# simple-door-controller-12v-rly-v1.net
KiCad netlist of a schematic drawn in EAGLE
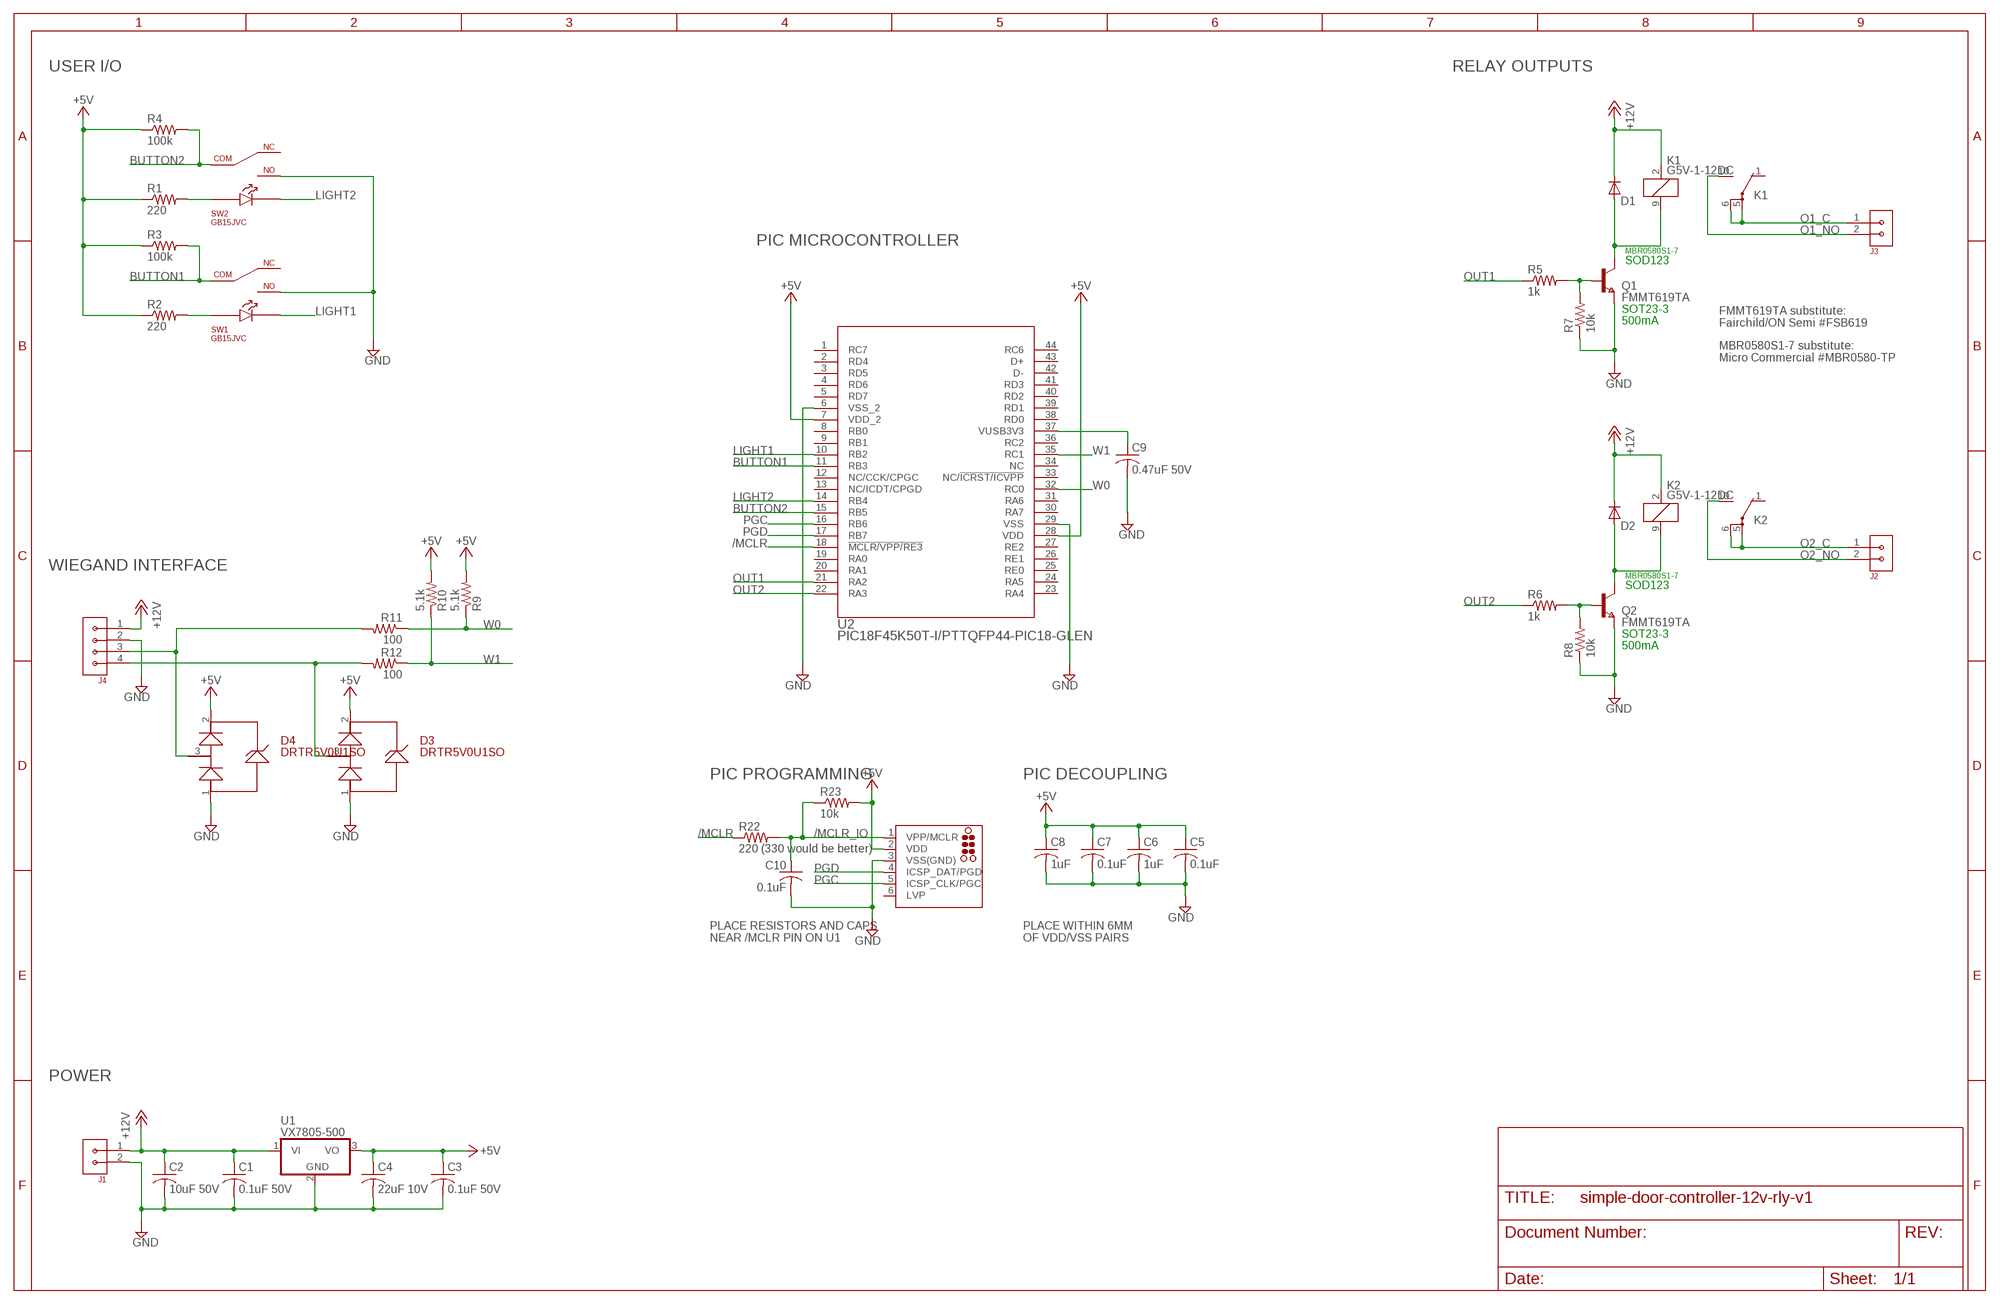
[diagram p0: schematic, sheet 1]

(export (version "E")
  (design (tool "Eeschema 10.0.6"))
  (components
    (comp (ref "C1")
      (value "0.1uF 50V")
      (footprint "eagle-import:C1206K")
      (fields (field (name "MFR") "KEMET") (field (name "MFR_PART_NO") "C1206S104M5RACTU"))
      (libsource (lib "eagle-import") (part "C-USC1206K"))
    )
    (comp (ref "C2")
      (value "10uF 50V")
      (footprint "eagle-import:C1210K")
      (fields (field (name "MFR") "KEMET") (field (name "MFR_PART_NO") "C1210C106K5RACTU"))
      (libsource (lib "eagle-import") (part "C-USC1210K"))
    )
    (comp (ref "C3")
      (value "0.1uF 50V")
      (footprint "eagle-import:C1206K")
      (fields (field (name "MFR") "KEMET") (field (name "MFR_PART_NO") "C1206S104M5RACTU"))
      (libsource (lib "eagle-import") (part "C-USC1206K"))
    )
    (comp (ref "C4")
      (value "22uF 10V")
      (footprint "eagle-import:C1206K")
      (fields (field (name "MFR") "KEMET") (field (name "MFR_PART_NO") "C1206C226K8RAC7800"))
      (libsource (lib "eagle-import") (part "C-USC1206K"))
    )
    (comp (ref "C5")
      (value "0.1uF")
      (footprint "eagle-import:C0603K")
      (libsource (lib "eagle-import") (part "C-USC0603K"))
    )
    (comp (ref "C6")
      (value "1uF")
      (footprint "eagle-import:C0603K")
      (libsource (lib "eagle-import") (part "C-USC0603K"))
    )
    (comp (ref "C7")
      (value "0.1uF")
      (footprint "eagle-import:C0603K")
      (libsource (lib "eagle-import") (part "C-USC0603K"))
    )
    (comp (ref "C8")
      (value "1uF")
      (footprint "eagle-import:C0603K")
      (libsource (lib "eagle-import") (part "C-USC0603K"))
    )
    (comp (ref "C9")
      (value "0.47uF 50V")
      (footprint "eagle-import:C1206K")
      (fields (field (name "MFR") "KEMET") (field (name "MFR_PART_NO") "C1206C474K5RACTU"))
      (libsource (lib "eagle-import") (part "C-USC1206K"))
    )
    (comp (ref "C10")
      (value "0.1uF")
      (footprint "eagle-import:C0603K")
      (libsource (lib "eagle-import") (part "C-USC0603K"))
    )
    (comp (ref "D1")
      (value "1N4148W-TP")
      (footprint "eagle-import:SOD123")
      (fields (field (name "MFR") "DIODES INC") (field (name "MFR_PART_NO") "MBR0580S1-7"))
      (libsource (lib "eagle-import") (part "DIODE-SOD123"))
    )
    (comp (ref "D2")
      (value "1N4148W-TP")
      (footprint "eagle-import:SOD123")
      (fields (field (name "MFR") "DIODES INC") (field (name "MFR_PART_NO") "MBR0580S1-7"))
      (libsource (lib "eagle-import") (part "DIODE-SOD123"))
    )
    (comp (ref "D3")
      (value "DRTR5V0U1SO")
      (footprint "eagle-import:SOT23-3")
      (libsource (lib "eagle-import") (part "DRTR5V0U1SO"))
    )
    (comp (ref "D4")
      (value "DRTR5V0U1SO")
      (footprint "eagle-import:SOT23-3")
      (libsource (lib "eagle-import") (part "DRTR5V0U1SO"))
    )
    (comp (ref "DEBUG")
      (value "TC2030-MCP-NL")
      (footprint "eagle-import:TC2030-MCP-NL")
      (libsource (lib "eagle-import") (part "TC2030-MCP-NL"))
    )
    (comp (ref "J1")
      (value "CON-3.81MM-1X2-PHOENIX")
      (footprint "eagle-import:CON-PHOENIX-3.81-1X2-RA")
      (libsource (lib "eagle-import") (part "CON-3.81MM-1X2-PHOENIX"))
    )
    (comp (ref "J2")
      (value "CON-3.81MM-1X2-PHOENIX")
      (footprint "eagle-import:CON-PHOENIX-3.81-1X2-RA")
      (libsource (lib "eagle-import") (part "CON-3.81MM-1X2-PHOENIX"))
    )
    (comp (ref "J3")
      (value "CON-3.81MM-1X2-PHOENIX")
      (footprint "eagle-import:CON-PHOENIX-3.81-1X2-RA")
      (libsource (lib "eagle-import") (part "CON-3.81MM-1X2-PHOENIX"))
    )
    (comp (ref "J4")
      (value "CON-3.81MM-1X4-PHOENIX-1803293")
      (footprint "eagle-import:CON-PHOENIX-1803293-3.81-1X4")
      (libsource (lib "eagle-import") (part "CON-3.81MM-1X4-PHOENIX-1803293"))
    )
    (comp (ref "K1")
      (value "G5V-1-12DC")
      (footprint "eagle-import:G5V1")
      (fields
        (field (name "MPN") "G5V-1-DC24")
        (field (name "MFR") "OMRON")
        (field (name "MFR_PART_NO") "G5V-1-DC5")
      )
      (libsource (lib "eagle-import") (part "G5V1"))
    )
    (comp (ref "K2")
      (value "G5V-1-12DC")
      (footprint "eagle-import:G5V1")
      (fields
        (field (name "MPN") "G5V-1-DC24")
        (field (name "MFR") "OMRON")
        (field (name "MFR_PART_NO") "G5V-1-DC5")
      )
      (libsource (lib "eagle-import") (part "G5V1"))
    )
    (comp (ref "Q1")
      (value "FMMT619TA")
      (footprint "eagle-import:SOT-23")
      (fields (field (name "MPN") "DSS20201L-7") (field (name "MFR") "DIODES INC"))
      (libsource (lib "eagle-import") (part "NPNSOT23"))
    )
    (comp (ref "Q2")
      (value "FMMT619TA")
      (footprint "eagle-import:SOT-23")
      (fields (field (name "MPN") "DSS20201L-7") (field (name "MFR") "DIODES INC"))
      (libsource (lib "eagle-import") (part "NPNSOT23"))
    )
    (comp (ref "R1")
      (value "220")
      (footprint "eagle-import:R0603")
      (libsource (lib "eagle-import") (part "R-US_R0603"))
    )
    (comp (ref "R2")
      (value "220")
      (footprint "eagle-import:R0603")
      (libsource (lib "eagle-import") (part "R-US_R0603"))
    )
    (comp (ref "R3")
      (value "100k")
      (footprint "eagle-import:R0603")
      (libsource (lib "eagle-import") (part "R-US_R0603"))
    )
    (comp (ref "R4")
      (value "100k")
      (footprint "eagle-import:R0603")
      (libsource (lib "eagle-import") (part "R-US_R0603"))
    )
    (comp (ref "R5")
      (value "1k")
      (footprint "eagle-import:R0603")
      (fields (field (name "MFR") "BOURNS") (field (name "MFR_PART_NO") "CR1206-JW-102ELF"))
      (libsource (lib "eagle-import") (part "R-US_R0603"))
    )
    (comp (ref "R6")
      (value "1k")
      (footprint "eagle-import:R0603")
      (fields (field (name "MFR") "BOURNS") (field (name "MFR_PART_NO") "CR1206-JW-102ELF"))
      (libsource (lib "eagle-import") (part "R-US_R0603"))
    )
    (comp (ref "R7")
      (value "10k")
      (footprint "eagle-import:R0603")
      (fields (field (name "MFR") "BOURNS") (field (name "MFR_PART_NO") "CR1206-JW-102ELF"))
      (libsource (lib "eagle-import") (part "R-US_R0603"))
    )
    (comp (ref "R8")
      (value "10k")
      (footprint "eagle-import:R0603")
      (fields (field (name "MFR") "BOURNS") (field (name "MFR_PART_NO") "CR1206-JW-102ELF"))
      (libsource (lib "eagle-import") (part "R-US_R0603"))
    )
    (comp (ref "R9")
      (value "5.1k")
      (footprint "eagle-import:R0603")
      (fields (field (name "MFR") "BOURNS") (field (name "MFR_PART_NO") "CR1206-JW-102ELF"))
      (libsource (lib "eagle-import") (part "R-US_R0603"))
    )
    (comp (ref "R10")
      (value "5.1k")
      (footprint "eagle-import:R0603")
      (fields (field (name "MFR") "BOURNS") (field (name "MFR_PART_NO") "CR1206-JW-102ELF"))
      (libsource (lib "eagle-import") (part "R-US_R0603"))
    )
    (comp (ref "R11")
      (value "100")
      (footprint "eagle-import:R0603")
      (fields (field (name "MFR") "BOURNS") (field (name "MFR_PART_NO") "CR1206-JW-102ELF"))
      (libsource (lib "eagle-import") (part "R-US_R0603"))
    )
    (comp (ref "R12")
      (value "100")
      (footprint "eagle-import:R0603")
      (fields (field (name "MFR") "BOURNS") (field (name "MFR_PART_NO") "CR1206-JW-102ELF"))
      (libsource (lib "eagle-import") (part "R-US_R0603"))
    )
    (comp (ref "R22")
      (value "220 (330 would be better)")
      (footprint "eagle-import:R0603")
      (libsource (lib "eagle-import") (part "R-US_R0603"))
    )
    (comp (ref "R23")
      (value "10k")
      (footprint "eagle-import:R0603")
      (libsource (lib "eagle-import") (part "R-US_R0603"))
    )
    (comp (ref "SW1")
      (value "GB15JVC")
      (footprint "eagle-import:GB15JHC")
      (libsource (lib "eagle-import") (part "GB15JHC"))
    )
    (comp (ref "SW2")
      (value "GB15JVC")
      (footprint "eagle-import:GB15JHC")
      (libsource (lib "eagle-import") (part "GB15JHC"))
    )
    (comp (ref "U1")
      (value "VX7805-500")
      (footprint "eagle-import:CUI-78XX-500")
      (libsource (lib "eagle-import") (part "CUI-V7803-500"))
    )
    (comp (ref "U2")
      (value "PIC18F45K50T-I/PTTQFP44-PIC18-GLEN")
      (footprint "eagle-import:TQFP44-PIC18-GLEN")
      (libsource (lib "eagle-import") (part "PIC18F45K50T-I/PTTQFP44-PIC18-GLEN"))
    )
  )
  (nets
    (net (code "1") (name "+5V") (class "Default")
      (node (ref "C3") (pin "1") (pinfunction "1_1") (pintype "passive"))
      (node (ref "C4") (pin "1") (pinfunction "1_1") (pintype "passive"))
      (node (ref "C5") (pin "1") (pinfunction "1_1") (pintype "passive"))
      (node (ref "C6") (pin "1") (pinfunction "1_1") (pintype "passive"))
      (node (ref "C7") (pin "1") (pinfunction "1_1") (pintype "passive"))
      (node (ref "C8") (pin "1") (pinfunction "1_1") (pintype "passive"))
      (node (ref "D3") (pin "2") (pinfunction "2_2") (pintype "bidirectional"))
      (node (ref "D4") (pin "2") (pinfunction "2_2") (pintype "bidirectional"))
      (node (ref "DEBUG") (pin "2") (pinfunction "VDD_2") (pintype "power_in"))
      (node (ref "R1") (pin "1") (pinfunction "1_1") (pintype "passive"))
      (node (ref "R10") (pin "2") (pinfunction "2_2") (pintype "passive"))
      (node (ref "R2") (pin "1") (pinfunction "1_1") (pintype "passive"))
      (node (ref "R23") (pin "2") (pinfunction "2_2") (pintype "passive"))
      (node (ref "R3") (pin "1") (pinfunction "1_1") (pintype "passive"))
      (node (ref "R4") (pin "1") (pinfunction "1_1") (pintype "passive"))
      (node (ref "R9") (pin "2") (pinfunction "2_2") (pintype "passive"))
      (node (ref "U1") (pin "3") (pinfunction "VO_3") (pintype "passive"))
      (node (ref "U2") (pin "28") (pinfunction "VDD_28") (pintype "power_in"))
      (node (ref "U2") (pin "7") (pinfunction "VDD_2_7") (pintype "power_in"))
    )
    (net (code "2") (name "+12V") (class "Default")
      (node (ref "C1") (pin "1") (pinfunction "1_1") (pintype "passive"))
      (node (ref "C2") (pin "1") (pinfunction "1_1") (pintype "passive"))
      (node (ref "D1") (pin "C") (pinfunction "C_C") (pintype "passive"))
      (node (ref "D2") (pin "C") (pinfunction "C_C") (pintype "passive"))
      (node (ref "J1") (pin "1") (pinfunction "1_1") (pintype "bidirectional"))
      (node (ref "J4") (pin "1") (pinfunction "1_1") (pintype "bidirectional"))
      (node (ref "K1") (pin "2") (pinfunction "1_2") (pintype "passive"))
      (node (ref "K2") (pin "2") (pinfunction "1_2") (pintype "passive"))
      (node (ref "U1") (pin "1") (pinfunction "VI_1") (pintype "input"))
    )
    (net (code "3") (name "/BUTTON1") (class "Default")
      (node (ref "R3") (pin "2") (pinfunction "2_2") (pintype "passive"))
      (node (ref "SW1") (pin "5") (pinfunction "5_5") (pintype "bidirectional"))
      (node (ref "U2") (pin "11") (pinfunction "RB3_11") (pintype "bidirectional"))
    )
    (net (code "4") (name "/BUTTON2") (class "Default")
      (node (ref "R4") (pin "2") (pinfunction "2_2") (pintype "passive"))
      (node (ref "SW2") (pin "5") (pinfunction "5_5") (pintype "bidirectional"))
      (node (ref "U2") (pin "15") (pinfunction "RB5_15") (pintype "bidirectional"))
    )
    (net (code "5") (name "/LIGHT1") (class "Default")
      (node (ref "SW1") (pin "3") (pinfunction "3_3") (pintype "bidirectional"))
      (node (ref "U2") (pin "10") (pinfunction "RB2_10") (pintype "bidirectional"))
    )
    (net (code "6") (name "/LIGHT2") (class "Default")
      (node (ref "SW2") (pin "3") (pinfunction "3_3") (pintype "bidirectional"))
      (node (ref "U2") (pin "14") (pinfunction "RB4_14") (pintype "bidirectional"))
    )
    (net (code "7") (name "/O1_C") (class "Default")
      (node (ref "J3") (pin "1") (pinfunction "1_1") (pintype "bidirectional"))
      (node (ref "K1") (pin "5") (pinfunction "P_5") (pintype "passive"))
      (node (ref "K1") (pin "6") (pinfunction "P_6") (pintype "passive"))
    )
    (net (code "8") (name "/O1_NO") (class "Default")
      (node (ref "J3") (pin "2") (pinfunction "2_2") (pintype "bidirectional"))
      (node (ref "K1") (pin "10") (pinfunction "S_10") (pintype "passive"))
    )
    (net (code "9") (name "/O2_C") (class "Default")
      (node (ref "J2") (pin "1") (pinfunction "1_1") (pintype "bidirectional"))
      (node (ref "K2") (pin "5") (pinfunction "P_5") (pintype "passive"))
      (node (ref "K2") (pin "6") (pinfunction "P_6") (pintype "passive"))
    )
    (net (code "10") (name "/O2_NO") (class "Default")
      (node (ref "J2") (pin "2") (pinfunction "2_2") (pintype "bidirectional"))
      (node (ref "K2") (pin "10") (pinfunction "S_10") (pintype "passive"))
    )
    (net (code "11") (name "/OUT1") (class "Default")
      (node (ref "R5") (pin "1") (pinfunction "1_1") (pintype "passive"))
      (node (ref "U2") (pin "21") (pinfunction "RA2_21") (pintype "bidirectional"))
    )
    (net (code "12") (name "/OUT2") (class "Default")
      (node (ref "R6") (pin "1") (pinfunction "1_1") (pintype "passive"))
      (node (ref "U2") (pin "22") (pinfunction "RA3_22") (pintype "bidirectional"))
    )
    (net (code "13") (name "/PGC") (class "Default")
      (node (ref "DEBUG") (pin "5") (pinfunction "ICSP_CLK/PGC_5") (pintype "output"))
      (node (ref "U2") (pin "16") (pinfunction "RB6_16") (pintype "bidirectional"))
    )
    (net (code "14") (name "/PGD") (class "Default")
      (node (ref "DEBUG") (pin "4") (pinfunction "ICSP_DAT/PGD_4") (pintype "bidirectional"))
      (node (ref "U2") (pin "17") (pinfunction "RB7_17") (pintype "bidirectional"))
    )
    (net (code "15") (name "/W0") (class "Default")
      (node (ref "R11") (pin "1") (pinfunction "1_1") (pintype "passive"))
      (node (ref "R9") (pin "1") (pinfunction "1_1") (pintype "passive"))
      (node (ref "U2") (pin "32") (pinfunction "RC0_32") (pintype "bidirectional"))
    )
    (net (code "16") (name "/W1") (class "Default")
      (node (ref "R10") (pin "1") (pinfunction "1_1") (pintype "passive"))
      (node (ref "R12") (pin "1") (pinfunction "1_1") (pintype "passive"))
      (node (ref "U2") (pin "35") (pinfunction "RC1_35") (pintype "bidirectional"))
    )
    (net (code "17") (name "/{slash}MCLR") (class "Default")
      (node (ref "R22") (pin "1") (pinfunction "1_1") (pintype "passive"))
      (node (ref "U2") (pin "18") (pinfunction "~{MCLR/VPP/RE3}_18") (pintype "bidirectional"))
    )
    (net (code "18") (name "/{slash}MCLR_IO") (class "Default")
      (node (ref "C10") (pin "1") (pinfunction "1_1") (pintype "passive"))
      (node (ref "DEBUG") (pin "1") (pinfunction "VPP/MCLR_1") (pintype "passive"))
      (node (ref "R22") (pin "2") (pinfunction "2_2") (pintype "passive"))
      (node (ref "R23") (pin "1") (pinfunction "1_1") (pintype "passive"))
    )
    (net (code "19") (name "GND") (class "Default")
      (node (ref "C1") (pin "2") (pinfunction "2_2") (pintype "passive"))
      (node (ref "C10") (pin "2") (pinfunction "2_2") (pintype "passive"))
      (node (ref "C2") (pin "2") (pinfunction "2_2") (pintype "passive"))
      (node (ref "C3") (pin "2") (pinfunction "2_2") (pintype "passive"))
      (node (ref "C4") (pin "2") (pinfunction "2_2") (pintype "passive"))
      (node (ref "C5") (pin "2") (pinfunction "2_2") (pintype "passive"))
      (node (ref "C6") (pin "2") (pinfunction "2_2") (pintype "passive"))
      (node (ref "C7") (pin "2") (pinfunction "2_2") (pintype "passive"))
      (node (ref "C8") (pin "2") (pinfunction "2_2") (pintype "passive"))
      (node (ref "C9") (pin "2") (pinfunction "2_2") (pintype "passive"))
      (node (ref "D3") (pin "1") (pinfunction "3_1") (pintype "bidirectional"))
      (node (ref "D4") (pin "1") (pinfunction "3_1") (pintype "bidirectional"))
      (node (ref "DEBUG") (pin "3") (pinfunction "VSS(GND)_3") (pintype "power_in"))
      (node (ref "J1") (pin "2") (pinfunction "2_2") (pintype "bidirectional"))
      (node (ref "J4") (pin "2") (pinfunction "2_2") (pintype "bidirectional"))
      (node (ref "Q1") (pin "2") (pinfunction "E_2") (pintype "passive"))
      (node (ref "Q2") (pin "2") (pinfunction "E_2") (pintype "passive"))
      (node (ref "R7") (pin "1") (pinfunction "1_1") (pintype "passive"))
      (node (ref "R8") (pin "1") (pinfunction "1_1") (pintype "passive"))
      (node (ref "SW1") (pin "4") (pinfunction "4_4") (pintype "bidirectional"))
      (node (ref "SW2") (pin "4") (pinfunction "4_4") (pintype "bidirectional"))
      (node (ref "U1") (pin "2") (pinfunction "GND_2") (pintype "passive"))
      (node (ref "U2") (pin "29") (pinfunction "VSS_29") (pintype "power_in"))
      (node (ref "U2") (pin "6") (pinfunction "VSS_2_6") (pintype "power_in"))
    )
    (net (code "20") (name "Net-(D3-1)") (class "Default")
      (node (ref "D3") (pin "3") (pinfunction "1_3") (pintype "bidirectional"))
      (node (ref "J4") (pin "4") (pinfunction "4_4") (pintype "bidirectional"))
      (node (ref "R12") (pin "2") (pinfunction "2_2") (pintype "passive"))
    )
    (net (code "21") (name "Net-(D4-1)") (class "Default")
      (node (ref "D4") (pin "3") (pinfunction "1_3") (pintype "bidirectional"))
      (node (ref "J4") (pin "3") (pinfunction "3_3") (pintype "bidirectional"))
      (node (ref "R11") (pin "2") (pinfunction "2_2") (pintype "passive"))
    )
    (net (code "22") (name "Net-(K1A-2)") (class "Default")
      (node (ref "D1") (pin "A") (pinfunction "A_A") (pintype "passive"))
      (node (ref "K1") (pin "9") (pinfunction "2_9") (pintype "passive"))
      (node (ref "Q1") (pin "1") (pinfunction "C_1") (pintype "passive"))
    )
    (net (code "23") (name "Net-(K2A-2)") (class "Default")
      (node (ref "D2") (pin "A") (pinfunction "A_A") (pintype "passive"))
      (node (ref "K2") (pin "9") (pinfunction "2_9") (pintype "passive"))
      (node (ref "Q2") (pin "1") (pinfunction "C_1") (pintype "passive"))
    )
    (net (code "24") (name "Net-(Q1-B)") (class "Default")
      (node (ref "Q1") (pin "3") (pinfunction "B_3") (pintype "passive"))
      (node (ref "R5") (pin "2") (pinfunction "2_2") (pintype "passive"))
      (node (ref "R7") (pin "2") (pinfunction "2_2") (pintype "passive"))
    )
    (net (code "25") (name "Net-(Q2-B)") (class "Default")
      (node (ref "Q2") (pin "3") (pinfunction "B_3") (pintype "passive"))
      (node (ref "R6") (pin "2") (pinfunction "2_2") (pintype "passive"))
      (node (ref "R8") (pin "2") (pinfunction "2_2") (pintype "passive"))
    )
    (net (code "26") (name "Net-(R1-Pad2)") (class "Default")
      (node (ref "R1") (pin "2") (pinfunction "2_2") (pintype "passive"))
      (node (ref "SW2") (pin "1") (pinfunction "1_1") (pintype "bidirectional"))
    )
    (net (code "27") (name "Net-(R2-Pad2)") (class "Default")
      (node (ref "R2") (pin "2") (pinfunction "2_2") (pintype "passive"))
      (node (ref "SW1") (pin "1") (pinfunction "1_1") (pintype "bidirectional"))
    )
    (net (code "28") (name "Net-(U2-VUSB3V3)") (class "Default")
      (node (ref "C9") (pin "1") (pinfunction "1_1") (pintype "passive"))
      (node (ref "U2") (pin "37") (pinfunction "VUSB3V3_37") (pintype "power_in"))
    )
    (net (code "29") (name "unconnected-(DEBUG-LVP-Pad6)") (class "Default")
      (node (ref "DEBUG") (pin "6") (pinfunction "LVP_6") (pintype "bidirectional"))
    )
    (net (code "30") (name "unconnected-(K1B-O-Pad1)") (class "Default")
      (node (ref "K1") (pin "1") (pinfunction "O_1") (pintype "passive"))
    )
    (net (code "31") (name "unconnected-(K2B-O-Pad1)") (class "Default")
      (node (ref "K2") (pin "1") (pinfunction "O_1") (pintype "passive"))
    )
    (net (code "32") (name "unconnected-(SW1-Pad6)") (class "Default")
      (node (ref "SW1") (pin "6") (pinfunction "6_6") (pintype "bidirectional"))
    )
    (net (code "33") (name "unconnected-(SW2-Pad6)") (class "Default")
      (node (ref "SW2") (pin "6") (pinfunction "6_6") (pintype "bidirectional"))
    )
    (net (code "34") (name "unconnected-(U2-D+-Pad43)") (class "Default")
      (node (ref "U2") (pin "43") (pinfunction "D+_43") (pintype "passive"))
    )
    (net (code "35") (name "unconnected-(U2-D--Pad42)") (class "Default")
      (node (ref "U2") (pin "42") (pinfunction "D-_42") (pintype "passive"))
    )
    (net (code "36") (name "unconnected-(U2-NC-Pad34)") (class "Default")
      (node (ref "U2") (pin "34") (pinfunction "NC_34") (pintype "no_connect"))
    )
    (net (code "37") (name "unconnected-(U2-NC{slash}CCK{slash}CPGC-Pad12)") (class "Default")
      (node (ref "U2") (pin "12") (pinfunction "NC/CCK/CPGC_12") (pintype "bidirectional"))
    )
    (net (code "38") (name "unconnected-(U2-NC{slash}ICDT{slash}CPGD-Pad13)") (class "Default")
      (node (ref "U2") (pin "13") (pinfunction "NC/ICDT/CPGD_13") (pintype "bidirectional"))
    )
    (net (code "39") (name "unconnected-(U2-NC{slash}~{ICRST{slash}ICVPP}-Pad33)") (class "Default")
      (node (ref "U2") (pin "33") (pinfunction "NC/~{ICRST/ICVPP}_33") (pintype "bidirectional"))
    )
    (net (code "40") (name "unconnected-(U2-RA0-Pad19)") (class "Default")
      (node (ref "U2") (pin "19") (pinfunction "RA0_19") (pintype "bidirectional"))
    )
    (net (code "41") (name "unconnected-(U2-RA1-Pad20)") (class "Default")
      (node (ref "U2") (pin "20") (pinfunction "RA1_20") (pintype "bidirectional"))
    )
    (net (code "42") (name "unconnected-(U2-RA4-Pad23)") (class "Default")
      (node (ref "U2") (pin "23") (pinfunction "RA4_23") (pintype "bidirectional"))
    )
    (net (code "43") (name "unconnected-(U2-RA5-Pad24)") (class "Default")
      (node (ref "U2") (pin "24") (pinfunction "RA5_24") (pintype "bidirectional"))
    )
    (net (code "44") (name "unconnected-(U2-RA6-Pad31)") (class "Default")
      (node (ref "U2") (pin "31") (pinfunction "RA6_31") (pintype "bidirectional"))
    )
    (net (code "45") (name "unconnected-(U2-RA7-Pad30)") (class "Default")
      (node (ref "U2") (pin "30") (pinfunction "RA7_30") (pintype "bidirectional"))
    )
    (net (code "46") (name "unconnected-(U2-RB0-Pad8)") (class "Default")
      (node (ref "U2") (pin "8") (pinfunction "RB0_8") (pintype "bidirectional"))
    )
    (net (code "47") (name "unconnected-(U2-RB1-Pad9)") (class "Default")
      (node (ref "U2") (pin "9") (pinfunction "RB1_9") (pintype "bidirectional"))
    )
    (net (code "48") (name "unconnected-(U2-RC2-Pad36)") (class "Default")
      (node (ref "U2") (pin "36") (pinfunction "RC2_36") (pintype "bidirectional"))
    )
    (net (code "49") (name "unconnected-(U2-RC6-Pad44)") (class "Default")
      (node (ref "U2") (pin "44") (pinfunction "RC6_44") (pintype "bidirectional"))
    )
    (net (code "50") (name "unconnected-(U2-RC7-Pad1)") (class "Default")
      (node (ref "U2") (pin "1") (pinfunction "RC7_1") (pintype "bidirectional"))
    )
    (net (code "51") (name "unconnected-(U2-RD0-Pad38)") (class "Default")
      (node (ref "U2") (pin "38") (pinfunction "RD0_38") (pintype "bidirectional"))
    )
    (net (code "52") (name "unconnected-(U2-RD1-Pad39)") (class "Default")
      (node (ref "U2") (pin "39") (pinfunction "RD1_39") (pintype "bidirectional"))
    )
    (net (code "53") (name "unconnected-(U2-RD2-Pad40)") (class "Default")
      (node (ref "U2") (pin "40") (pinfunction "RD2_40") (pintype "bidirectional"))
    )
    (net (code "54") (name "unconnected-(U2-RD3-Pad41)") (class "Default")
      (node (ref "U2") (pin "41") (pinfunction "RD3_41") (pintype "bidirectional"))
    )
    (net (code "55") (name "unconnected-(U2-RD4-Pad2)") (class "Default")
      (node (ref "U2") (pin "2") (pinfunction "RD4_2") (pintype "bidirectional"))
    )
    (net (code "56") (name "unconnected-(U2-RD5-Pad3)") (class "Default")
      (node (ref "U2") (pin "3") (pinfunction "RD5_3") (pintype "bidirectional"))
    )
    (net (code "57") (name "unconnected-(U2-RD6-Pad4)") (class "Default")
      (node (ref "U2") (pin "4") (pinfunction "RD6_4") (pintype "bidirectional"))
    )
    (net (code "58") (name "unconnected-(U2-RD7-Pad5)") (class "Default")
      (node (ref "U2") (pin "5") (pinfunction "RD7_5") (pintype "bidirectional"))
    )
    (net (code "59") (name "unconnected-(U2-RE0-Pad25)") (class "Default")
      (node (ref "U2") (pin "25") (pinfunction "RE0_25") (pintype "bidirectional"))
    )
    (net (code "60") (name "unconnected-(U2-RE1-Pad26)") (class "Default")
      (node (ref "U2") (pin "26") (pinfunction "RE1_26") (pintype "bidirectional"))
    )
    (net (code "61") (name "unconnected-(U2-RE2-Pad27)") (class "Default")
      (node (ref "U2") (pin "27") (pinfunction "RE2_27") (pintype "bidirectional"))
    )
  )
)
